# seven_seg_thermistor_one.net
KiCad netlist of a schematic drawn in EAGLE
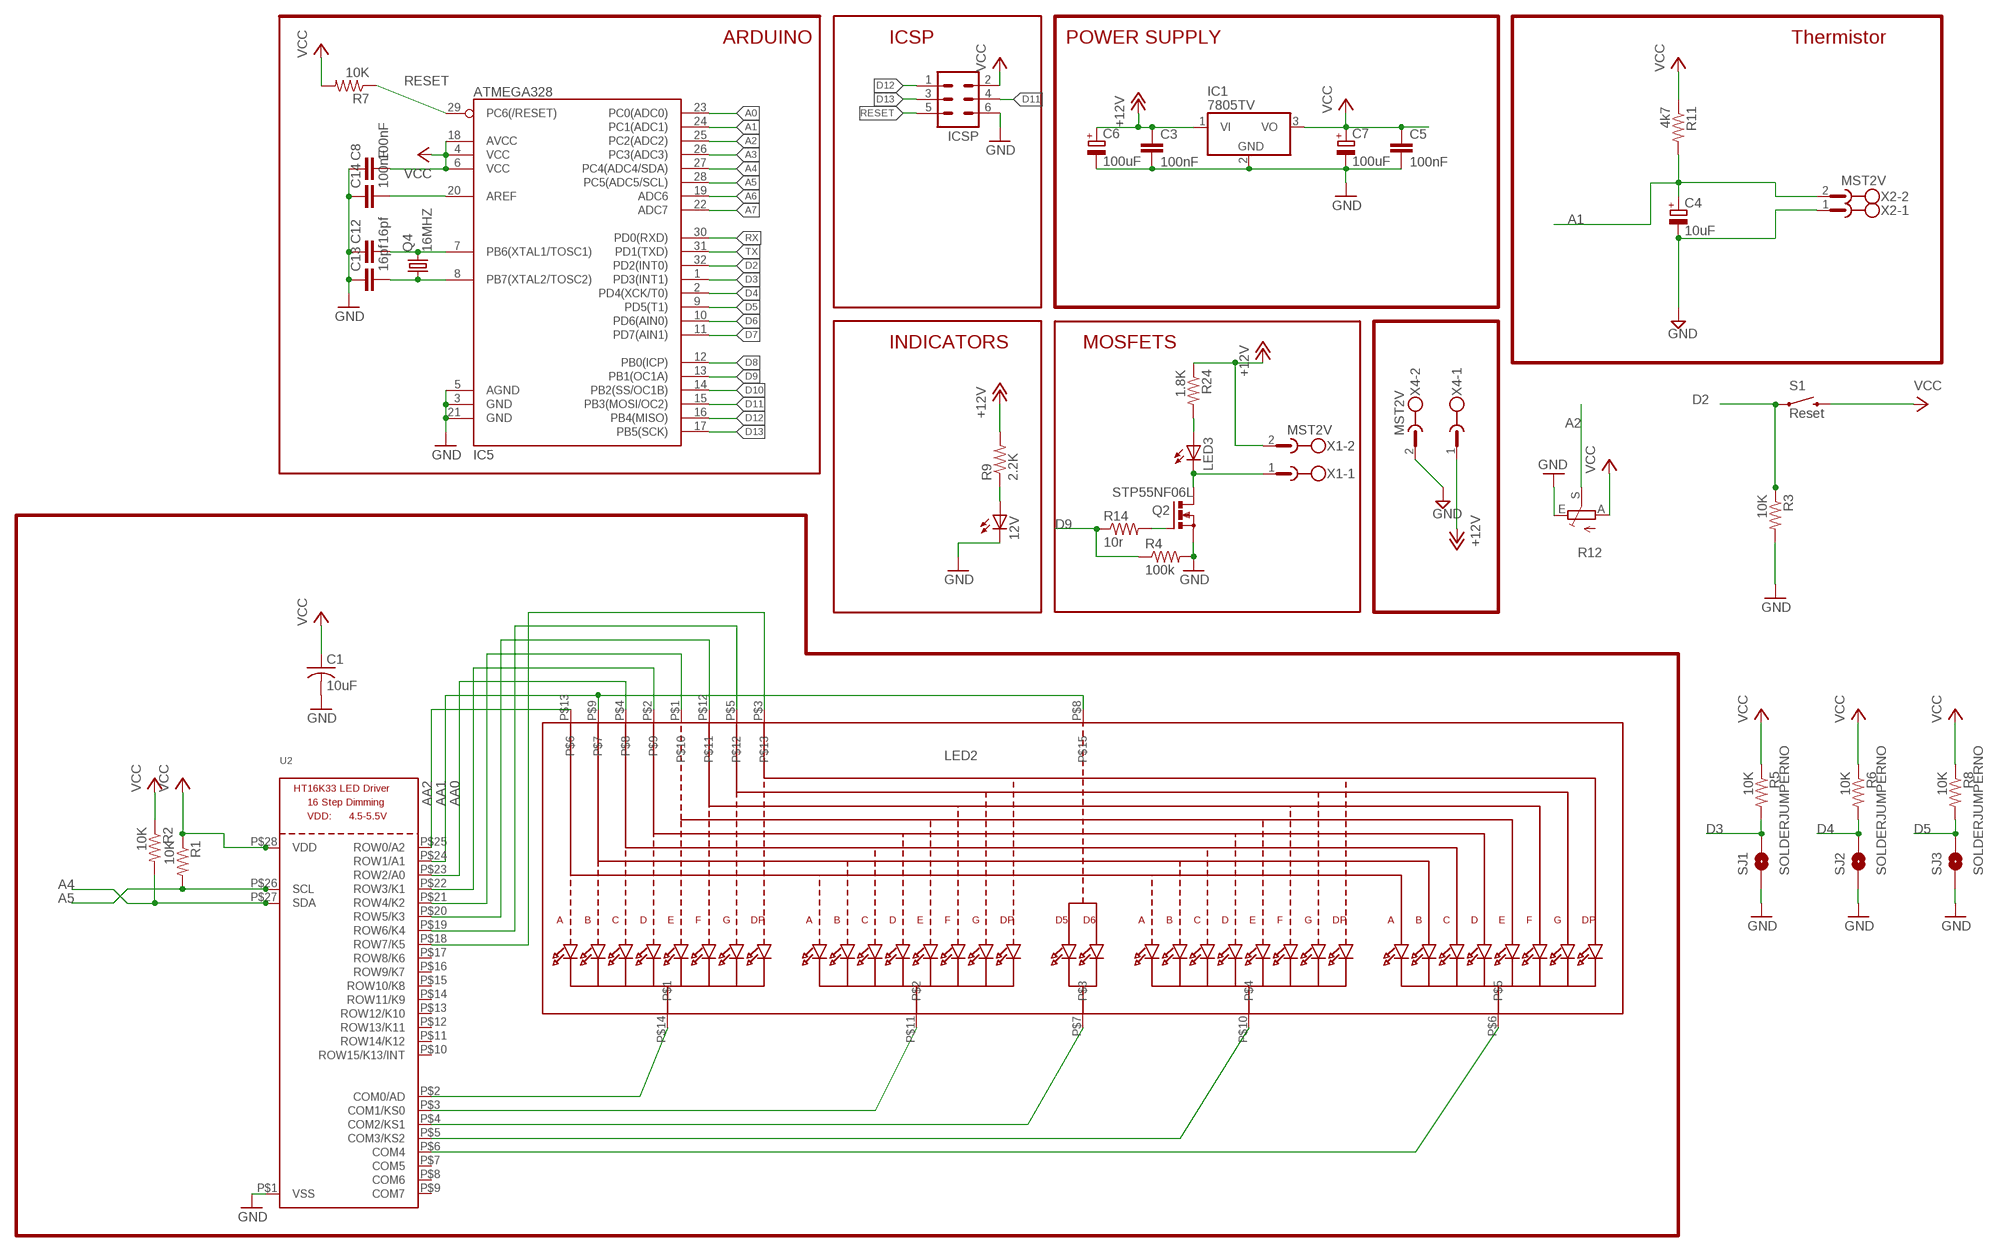
[diagram p0: schematic, sheet 1]

(export (version "E")
  (design (tool "Eeschema 10.0.6"))
  (components
    (comp (ref "12V")
      (value "LED0805")
      (footprint "eagle-import:LED-0805")
      (libsource (lib "eagle-import") (part "LED0805"))
    )
    (comp (ref "C1")
      (value "10uF")
      (footprint "eagle-import:C0805K")
      (libsource (lib "eagle-import") (part "C-USC0805K"))
    )
    (comp (ref "C3")
      (value "100nF")
      (footprint "eagle-import:0805")
      (libsource (lib "eagle-import") (part "CAP0805"))
    )
    (comp (ref "C4")
      (value "10uF")
      (footprint "eagle-import:E5-6")
      (libsource (lib "eagle-import") (part "CPOL-EUE5-6"))
    )
    (comp (ref "C5")
      (value "100nF")
      (footprint "eagle-import:0805")
      (libsource (lib "eagle-import") (part "CAP0805"))
    )
    (comp (ref "C6")
      (value "100uF")
      (footprint "eagle-import:E3,5-8")
      (libsource (lib "eagle-import") (part "CPOL-EUE3.5-8"))
    )
    (comp (ref "C7")
      (value "100uF")
      (footprint "eagle-import:E3,5-8")
      (libsource (lib "eagle-import") (part "CPOL-EUE3.5-8"))
    )
    (comp (ref "C8")
      (value "100nF")
      (footprint "eagle-import:0805")
      (libsource (lib "eagle-import") (part "CAP0805"))
    )
    (comp (ref "C12")
      (value "16pf")
      (footprint "eagle-import:0805")
      (libsource (lib "eagle-import") (part "CAP0805"))
    )
    (comp (ref "C13")
      (value "16pf")
      (footprint "eagle-import:0805")
      (libsource (lib "eagle-import") (part "CAP0805"))
    )
    (comp (ref "C14")
      (value "100nF")
      (footprint "eagle-import:0805")
      (libsource (lib "eagle-import") (part "CAP0805"))
    )
    (comp (ref "IC1")
      (value "7805TV")
      (footprint "eagle-import:TO220V")
      (libsource (lib "eagle-import") (part "78TV05"))
    )
    (comp (ref "IC5")
      (value "ATMEGA328")
      (footprint "eagle-import:TQFP32-08")
      (libsource (lib "eagle-import") (part "ATMEGA168"))
    )
    (comp (ref "ICSP")
      (value "ML6")
      (footprint "eagle-import:ML6")
      (libsource (lib "eagle-import") (part "ML6"))
    )
    (comp (ref "LED2")
      (value "DISP_SEGMENT_4DIGIT_BL-Q56C43")
      (footprint "eagle-import:SEGMENT-BL-Q56C43")
      (libsource (lib "eagle-import") (part "DISP_SEGMENT_4DIGIT_BL-Q56C43"))
    )
    (comp (ref "LED3")
      (value "LEDCHIP-LED0805")
      (footprint "eagle-import:CHIP-LED0805")
      (libsource (lib "eagle-import") (part "LEDCHIP-LED0805"))
    )
    (comp (ref "Q2")
      (value "STP55NF06L")
      (footprint "eagle-import:TO220BV")
      (libsource (lib "eagle-import") (part "IRF512"))
    )
    (comp (ref "Q4")
      (value "16MHZ")
      (footprint "eagle-import:HC49_S")
      (libsource (lib "eagle-import") (part "CRYSTALHC49S"))
    )
    (comp (ref "R1")
      (value "10K")
      (footprint "eagle-import:R0805")
      (libsource (lib "eagle-import") (part "R-US_R0805"))
    )
    (comp (ref "R2")
      (value "10K")
      (footprint "eagle-import:R0805")
      (libsource (lib "eagle-import") (part "R-US_R0805"))
    )
    (comp (ref "R3")
      (value "10K")
      (footprint "eagle-import:0805")
      (libsource (lib "eagle-import") (part "RESISTOR"))
    )
    (comp (ref "R4")
      (value "100k")
      (footprint "eagle-import:R0805")
      (libsource (lib "eagle-import") (part "R-US_R0805"))
    )
    (comp (ref "R5")
      (value "10K")
      (footprint "eagle-import:0805")
      (libsource (lib "eagle-import") (part "RESISTOR"))
    )
    (comp (ref "R6")
      (value "10K")
      (footprint "eagle-import:0805")
      (libsource (lib "eagle-import") (part "RESISTOR"))
    )
    (comp (ref "R7")
      (value "10K")
      (footprint "eagle-import:0805")
      (libsource (lib "eagle-import") (part "RESISTOR"))
    )
    (comp (ref "R8")
      (value "10K")
      (footprint "eagle-import:0805")
      (libsource (lib "eagle-import") (part "RESISTOR"))
    )
    (comp (ref "R9")
      (value "2.2K")
      (footprint "eagle-import:0805")
      (libsource (lib "eagle-import") (part "RESISTOR"))
    )
    (comp (ref "R11")
      (value "4k7")
      (footprint "eagle-import:0805")
      (libsource (lib "eagle-import") (part "RESISTOR"))
    )
    (comp (ref "R12")
      (value "TRIM_EU-B25U")
      (footprint "eagle-import:B25U")
      (libsource (lib "eagle-import") (part "TRIM_EU-B25U"))
    )
    (comp (ref "R14")
      (value "10r")
      (footprint "eagle-import:M0805")
      (libsource (lib "eagle-import") (part "resistor_R-US_M0805"))
    )
    (comp (ref "R24")
      (value "1.8K")
      (footprint "eagle-import:R0805")
      (libsource (lib "eagle-import") (part "R-US_R0805"))
    )
    (comp (ref "S1")
      (value "Reset")
      (footprint "eagle-import:TACTILE-SWITCH-SMD-ALT01")
      (libsource (lib "eagle-import") (part "SWITCH-MOMENTARY-2SMD-ALT01"))
    )
    (comp (ref "SJ1")
      (value "SOLDERJUMPERNO")
      (footprint "eagle-import:SJ_2S-NO")
      (libsource (lib "eagle-import") (part "SOLDERJUMPERNO"))
    )
    (comp (ref "SJ2")
      (value "SOLDERJUMPERNO")
      (footprint "eagle-import:SJ_2S-NO")
      (libsource (lib "eagle-import") (part "SOLDERJUMPERNO"))
    )
    (comp (ref "SJ3")
      (value "SOLDERJUMPERNO")
      (footprint "eagle-import:SJ_2S-NO")
      (libsource (lib "eagle-import") (part "SOLDERJUMPERNO"))
    )
    (comp (ref "U2")
      (value "HT16K33_SOP28")
      (footprint "eagle-import:SOP28_300MIL")
      (libsource (lib "eagle-import") (part "HT16K33_SOP28"))
    )
    (comp (ref "X1")
      (value "MST2V")
      (footprint "eagle-import:MSTBV2")
      (libsource (lib "eagle-import") (part "MST2V"))
    )
    (comp (ref "X2")
      (value "MST2V")
      (footprint "eagle-import:MSTBV2")
      (libsource (lib "eagle-import") (part "MST2V"))
    )
    (comp (ref "X4")
      (value "MST2V")
      (footprint "eagle-import:MSTBV2")
      (libsource (lib "eagle-import") (part "MST2V"))
    )
  )
  (nets
    (net (code "1") (name "+12V") (class "Default")
      (node (ref "C3") (pin "1") (pinfunction "1_1") (pintype "passive"))
      (node (ref "C6") (pin "+") (pinfunction "+_+") (pintype "passive"))
      (node (ref "IC1") (pin "1") (pinfunction "VI_1") (pintype "input"))
      (node (ref "R24") (pin "1") (pinfunction "1_1") (pintype "passive"))
      (node (ref "R9") (pin "2") (pinfunction "2_2") (pintype "passive"))
      (node (ref "X1") (pin "2") (pinfunction "1_2") (pintype "passive"))
      (node (ref "X4") (pin "1") (pinfunction "1_1") (pintype "passive"))
    )
    (net (code "2") (name "/AA0") (class "Default")
      (node (ref "LED2") (pin "P$4") (pinfunction "P$8_P$4") (pintype "bidirectional"))
      (node (ref "U2") (pin "P$23") (pinfunction "ROW2/A0_P$23") (pintype "bidirectional"))
    )
    (net (code "3") (name "/AA1") (class "Default")
      (node (ref "LED2") (pin "P$8") (pinfunction "P$15_P$8") (pintype "bidirectional"))
      (node (ref "LED2") (pin "P$9") (pinfunction "P$7_P$9") (pintype "bidirectional"))
      (node (ref "U2") (pin "P$24") (pinfunction "ROW1/A1_P$24") (pintype "bidirectional"))
    )
    (net (code "4") (name "/AA2") (class "Default")
      (node (ref "LED2") (pin "P$13") (pinfunction "P$6_P$13") (pintype "bidirectional"))
      (node (ref "U2") (pin "P$25") (pinfunction "ROW0/A2_P$25") (pintype "bidirectional"))
    )
    (net (code "5") (name "A0") (class "Default")
      (node (ref "IC5") (pin "23") (pinfunction "PC0(ADC0)_23") (pintype "bidirectional"))
    )
    (net (code "6") (name "A1") (class "Default")
      (node (ref "C4") (pin "+") (pinfunction "+_+") (pintype "passive"))
      (node (ref "IC5") (pin "24") (pinfunction "PC1(ADC1)_24") (pintype "bidirectional"))
      (node (ref "R11") (pin "2") (pinfunction "2_2") (pintype "passive"))
      (node (ref "X2") (pin "2") (pinfunction "1_2") (pintype "passive"))
    )
    (net (code "7") (name "A2") (class "Default")
      (node (ref "IC5") (pin "25") (pinfunction "PC2(ADC2)_25") (pintype "bidirectional"))
      (node (ref "R12") (pin "S") (pinfunction "S_S") (pintype "passive"))
    )
    (net (code "8") (name "A3") (class "Default")
      (node (ref "IC5") (pin "26") (pinfunction "PC3(ADC3)_26") (pintype "bidirectional"))
    )
    (net (code "9") (name "A4") (class "Default")
      (node (ref "IC5") (pin "27") (pinfunction "PC4(ADC4/SDA)_27") (pintype "bidirectional"))
      (node (ref "R2") (pin "2") (pinfunction "2_2") (pintype "passive"))
      (node (ref "U2") (pin "P$27") (pinfunction "SDA_P$27") (pintype "bidirectional"))
    )
    (net (code "10") (name "A5") (class "Default")
      (node (ref "IC5") (pin "28") (pinfunction "PC5(ADC5/SCL)_28") (pintype "bidirectional"))
      (node (ref "R1") (pin "2") (pinfunction "2_2") (pintype "passive"))
      (node (ref "U2") (pin "P$26") (pinfunction "SCL_P$26") (pintype "bidirectional"))
    )
    (net (code "11") (name "A6") (class "Default")
      (node (ref "IC5") (pin "19") (pinfunction "ADC6_19") (pintype "bidirectional"))
    )
    (net (code "12") (name "A7") (class "Default")
      (node (ref "IC5") (pin "22") (pinfunction "ADC7_22") (pintype "bidirectional"))
    )
    (net (code "13") (name "D2") (class "Default")
      (node (ref "IC5") (pin "32") (pinfunction "PD2(INT0)_32") (pintype "bidirectional"))
      (node (ref "R3") (pin "1") (pinfunction "1_1") (pintype "passive"))
      (node (ref "S1") (pin "1") (pinfunction "1_1") (pintype "passive"))
      (node (ref "S1") (pin "2") (pinfunction "1_2") (pintype "passive"))
    )
    (net (code "14") (name "D3") (class "Default")
      (node (ref "IC5") (pin "1") (pinfunction "PD3(INT1)_1") (pintype "bidirectional"))
      (node (ref "R5") (pin "2") (pinfunction "2_2") (pintype "passive"))
      (node (ref "SJ1") (pin "2") (pinfunction "2_2") (pintype "passive"))
    )
    (net (code "15") (name "D4") (class "Default")
      (node (ref "IC5") (pin "2") (pinfunction "PD4(XCK/T0)_2") (pintype "bidirectional"))
      (node (ref "R6") (pin "2") (pinfunction "2_2") (pintype "passive"))
      (node (ref "SJ2") (pin "2") (pinfunction "2_2") (pintype "passive"))
    )
    (net (code "16") (name "D5") (class "Default")
      (node (ref "IC5") (pin "9") (pinfunction "PD5(T1)_9") (pintype "bidirectional"))
      (node (ref "R8") (pin "2") (pinfunction "2_2") (pintype "passive"))
      (node (ref "SJ3") (pin "2") (pinfunction "2_2") (pintype "passive"))
    )
    (net (code "17") (name "D6") (class "Default")
      (node (ref "IC5") (pin "10") (pinfunction "PD6(AIN0)_10") (pintype "bidirectional"))
    )
    (net (code "18") (name "D7") (class "Default")
      (node (ref "IC5") (pin "11") (pinfunction "PD7(AIN1)_11") (pintype "bidirectional"))
    )
    (net (code "19") (name "D8") (class "Default")
      (node (ref "IC5") (pin "12") (pinfunction "PB0(ICP)_12") (pintype "bidirectional"))
    )
    (net (code "20") (name "D9") (class "Default")
      (node (ref "IC5") (pin "13") (pinfunction "PB1(OC1A)_13") (pintype "bidirectional"))
      (node (ref "R14") (pin "1") (pinfunction "1_1") (pintype "passive"))
      (node (ref "R4") (pin "1") (pinfunction "1_1") (pintype "passive"))
    )
    (net (code "21") (name "D10") (class "Default")
      (node (ref "IC5") (pin "14") (pinfunction "PB2(SS/OC1B)_14") (pintype "bidirectional"))
    )
    (net (code "22") (name "D11") (class "Default")
      (node (ref "IC5") (pin "15") (pinfunction "PB3(MOSI/OC2)_15") (pintype "bidirectional"))
      (node (ref "ICSP") (pin "4") (pinfunction "4_4") (pintype "passive"))
    )
    (net (code "23") (name "D12") (class "Default")
      (node (ref "IC5") (pin "16") (pinfunction "PB4(MISO)_16") (pintype "bidirectional"))
      (node (ref "ICSP") (pin "1") (pinfunction "1_1") (pintype "passive"))
    )
    (net (code "24") (name "D13") (class "Default")
      (node (ref "IC5") (pin "17") (pinfunction "PB5(SCK)_17") (pintype "bidirectional"))
      (node (ref "ICSP") (pin "3") (pinfunction "3_3") (pintype "passive"))
    )
    (net (code "25") (name "GND") (class "Default")
      (node (ref "12V") (pin "C") (pinfunction "C_C") (pintype "passive"))
      (node (ref "C1") (pin "2") (pinfunction "2_2") (pintype "passive"))
      (node (ref "C12") (pin "1") (pinfunction "1_1") (pintype "passive"))
      (node (ref "C13") (pin "1") (pinfunction "1_1") (pintype "passive"))
      (node (ref "C14") (pin "1") (pinfunction "1_1") (pintype "passive"))
      (node (ref "C3") (pin "2") (pinfunction "2_2") (pintype "passive"))
      (node (ref "C4") (pin "-") (pinfunction "-_-") (pintype "passive"))
      (node (ref "C5") (pin "2") (pinfunction "2_2") (pintype "passive"))
      (node (ref "C6") (pin "-") (pinfunction "-_-") (pintype "passive"))
      (node (ref "C7") (pin "-") (pinfunction "-_-") (pintype "passive"))
      (node (ref "C8") (pin "1") (pinfunction "1_1") (pintype "passive"))
      (node (ref "IC1") (pin "2") (pinfunction "GND_2") (pintype "passive"))
      (node (ref "IC5") (pin "21") (pinfunction "GND_21") (pintype "bidirectional"))
      (node (ref "IC5") (pin "3") (pinfunction "GND_3") (pintype "bidirectional"))
      (node (ref "IC5") (pin "5") (pinfunction "AGND_5") (pintype "bidirectional"))
      (node (ref "ICSP") (pin "6") (pinfunction "6_6") (pintype "passive"))
      (node (ref "Q2") (pin "S") (pinfunction "S_S") (pintype "passive"))
      (node (ref "R12") (pin "E") (pinfunction "E_E") (pintype "passive"))
      (node (ref "R3") (pin "2") (pinfunction "2_2") (pintype "passive"))
      (node (ref "R4") (pin "2") (pinfunction "2_2") (pintype "passive"))
      (node (ref "SJ1") (pin "1") (pinfunction "1_1") (pintype "passive"))
      (node (ref "SJ2") (pin "1") (pinfunction "1_1") (pintype "passive"))
      (node (ref "SJ3") (pin "1") (pinfunction "1_1") (pintype "passive"))
      (node (ref "U2") (pin "P$1") (pinfunction "VSS_P$1") (pintype "bidirectional"))
      (node (ref "X2") (pin "1") (pinfunction "1_1") (pintype "passive"))
      (node (ref "X4") (pin "2") (pinfunction "1_2") (pintype "passive"))
    )
    (net (code "26") (name "Net-(12V-PadA)") (class "Default")
      (node (ref "12V") (pin "A") (pinfunction "A_A") (pintype "passive"))
      (node (ref "R9") (pin "1") (pinfunction "1_1") (pintype "passive"))
    )
    (net (code "27") (name "Net-(IC5-AREF)") (class "Default")
      (node (ref "C14") (pin "2") (pinfunction "2_2") (pintype "passive"))
      (node (ref "IC5") (pin "20") (pinfunction "AREF_20") (pintype "bidirectional"))
    )
    (net (code "28") (name "Net-(IC5-PB6(XTAL1{slash}TOSC1))") (class "Default")
      (node (ref "C12") (pin "2") (pinfunction "2_2") (pintype "passive"))
      (node (ref "IC5") (pin "7") (pinfunction "PB6(XTAL1/TOSC1)_7") (pintype "bidirectional"))
      (node (ref "Q4") (pin "2") (pinfunction "2_2") (pintype "passive"))
    )
    (net (code "29") (name "Net-(IC5-PB7(XTAL2{slash}TOSC2))") (class "Default")
      (node (ref "C13") (pin "2") (pinfunction "2_2") (pintype "passive"))
      (node (ref "IC5") (pin "8") (pinfunction "PB7(XTAL2/TOSC2)_8") (pintype "bidirectional"))
      (node (ref "Q4") (pin "1") (pinfunction "1_1") (pintype "passive"))
    )
    (net (code "30") (name "Net-(LED2-P$1)") (class "Default")
      (node (ref "LED2") (pin "P$14") (pinfunction "P$1_P$14") (pintype "bidirectional"))
      (node (ref "U2") (pin "P$2") (pinfunction "COM0/AD_P$2") (pintype "bidirectional"))
    )
    (net (code "31") (name "Net-(LED2-P$2)") (class "Default")
      (node (ref "LED2") (pin "P$11") (pinfunction "P$2_P$11") (pintype "bidirectional"))
      (node (ref "U2") (pin "P$3") (pinfunction "COM1/KS0_P$3") (pintype "bidirectional"))
    )
    (net (code "32") (name "Net-(LED2-P$3)") (class "Default")
      (node (ref "LED2") (pin "P$7") (pinfunction "P$3_P$7") (pintype "bidirectional"))
      (node (ref "U2") (pin "P$4") (pinfunction "COM2/KS1_P$4") (pintype "bidirectional"))
    )
    (net (code "33") (name "Net-(LED2-P$4)") (class "Default")
      (node (ref "LED2") (pin "P$10") (pinfunction "P$4_P$10") (pintype "bidirectional"))
      (node (ref "U2") (pin "P$5") (pinfunction "COM3/KS2_P$5") (pintype "bidirectional"))
    )
    (net (code "34") (name "Net-(LED2-P$5)") (class "Default")
      (node (ref "LED2") (pin "P$6") (pinfunction "P$5_P$6") (pintype "bidirectional"))
      (node (ref "U2") (pin "P$6") (pinfunction "COM4_P$6") (pintype "bidirectional"))
    )
    (net (code "35") (name "Net-(LED2-P$9)") (class "Default")
      (node (ref "LED2") (pin "P$2") (pinfunction "P$9_P$2") (pintype "bidirectional"))
      (node (ref "U2") (pin "P$22") (pinfunction "ROW3/K1_P$22") (pintype "bidirectional"))
    )
    (net (code "36") (name "Net-(LED2-P$10)") (class "Default")
      (node (ref "LED2") (pin "P$1") (pinfunction "P$10_P$1") (pintype "bidirectional"))
      (node (ref "U2") (pin "P$21") (pinfunction "ROW4/K2_P$21") (pintype "bidirectional"))
    )
    (net (code "37") (name "Net-(LED2-P$11)") (class "Default")
      (node (ref "LED2") (pin "P$12") (pinfunction "P$11_P$12") (pintype "bidirectional"))
      (node (ref "U2") (pin "P$20") (pinfunction "ROW5/K3_P$20") (pintype "bidirectional"))
    )
    (net (code "38") (name "Net-(LED2-P$12)") (class "Default")
      (node (ref "LED2") (pin "P$5") (pinfunction "P$12_P$5") (pintype "bidirectional"))
      (node (ref "U2") (pin "P$19") (pinfunction "ROW6/K4_P$19") (pintype "bidirectional"))
    )
    (net (code "39") (name "Net-(LED2-P$13)") (class "Default")
      (node (ref "LED2") (pin "P$3") (pinfunction "P$13_P$3") (pintype "bidirectional"))
      (node (ref "U2") (pin "P$18") (pinfunction "ROW7/K5_P$18") (pintype "bidirectional"))
    )
    (net (code "40") (name "Net-(LED3-PadA)") (class "Default")
      (node (ref "LED3") (pin "A") (pinfunction "A_A") (pintype "passive"))
      (node (ref "R24") (pin "2") (pinfunction "2_2") (pintype "passive"))
    )
    (net (code "41") (name "Net-(LED3-PadC)") (class "Default")
      (node (ref "LED3") (pin "C") (pinfunction "C_C") (pintype "passive"))
      (node (ref "Q2") (pin "D") (pinfunction "D_D") (pintype "passive"))
      (node (ref "X1") (pin "1") (pinfunction "1_1") (pintype "passive"))
    )
    (net (code "42") (name "Net-(Q2-PadG)") (class "Default")
      (node (ref "Q2") (pin "G") (pinfunction "G_G") (pintype "passive"))
      (node (ref "R14") (pin "2") (pinfunction "2_2") (pintype "passive"))
    )
    (net (code "43") (name "RESET") (class "Default")
      (node (ref "IC5") (pin "29") (pinfunction "PC6(/RESET)_29") (pintype "bidirectional"))
      (node (ref "ICSP") (pin "5") (pinfunction "5_5") (pintype "passive"))
      (node (ref "R7") (pin "1") (pinfunction "1_1") (pintype "passive"))
    )
    (net (code "44") (name "RX") (class "Default")
      (node (ref "IC5") (pin "30") (pinfunction "PD0(RXD)_30") (pintype "bidirectional"))
    )
    (net (code "45") (name "TX") (class "Default")
      (node (ref "IC5") (pin "31") (pinfunction "PD1(TXD)_31") (pintype "bidirectional"))
    )
    (net (code "46") (name "VCC") (class "Default")
      (node (ref "C1") (pin "1") (pinfunction "1_1") (pintype "passive"))
      (node (ref "C5") (pin "1") (pinfunction "1_1") (pintype "passive"))
      (node (ref "C7") (pin "+") (pinfunction "+_+") (pintype "passive"))
      (node (ref "C8") (pin "2") (pinfunction "2_2") (pintype "passive"))
      (node (ref "IC1") (pin "3") (pinfunction "VO_3") (pintype "passive"))
      (node (ref "IC5") (pin "18") (pinfunction "AVCC_18") (pintype "bidirectional"))
      (node (ref "IC5") (pin "4") (pinfunction "VCC_4") (pintype "bidirectional"))
      (node (ref "IC5") (pin "6") (pinfunction "VCC_6") (pintype "bidirectional"))
      (node (ref "ICSP") (pin "2") (pinfunction "2_2") (pintype "passive"))
      (node (ref "R1") (pin "1") (pinfunction "1_1") (pintype "passive"))
      (node (ref "R11") (pin "1") (pinfunction "1_1") (pintype "passive"))
      (node (ref "R12") (pin "A") (pinfunction "A_A") (pintype "passive"))
      (node (ref "R2") (pin "1") (pinfunction "1_1") (pintype "passive"))
      (node (ref "R5") (pin "1") (pinfunction "1_1") (pintype "passive"))
      (node (ref "R6") (pin "1") (pinfunction "1_1") (pintype "passive"))
      (node (ref "R7") (pin "2") (pinfunction "2_2") (pintype "passive"))
      (node (ref "R8") (pin "1") (pinfunction "1_1") (pintype "passive"))
      (node (ref "S1") (pin "3") (pinfunction "2_3") (pintype "passive"))
      (node (ref "S1") (pin "4") (pinfunction "2_4") (pintype "passive"))
      (node (ref "U2") (pin "P$28") (pinfunction "VDD_P$28") (pintype "bidirectional"))
    )
    (net (code "47") (name "unconnected-(U2-COM5-PadP$7)") (class "Default")
      (node (ref "U2") (pin "P$7") (pinfunction "COM5_P$7") (pintype "bidirectional"))
    )
    (net (code "48") (name "unconnected-(U2-COM6-PadP$8)") (class "Default")
      (node (ref "U2") (pin "P$8") (pinfunction "COM6_P$8") (pintype "bidirectional"))
    )
    (net (code "49") (name "unconnected-(U2-COM7-PadP$9)") (class "Default")
      (node (ref "U2") (pin "P$9") (pinfunction "COM7_P$9") (pintype "bidirectional"))
    )
    (net (code "50") (name "unconnected-(U2-ROW8{slash}K6-PadP$17)") (class "Default")
      (node (ref "U2") (pin "P$17") (pinfunction "ROW8/K6_P$17") (pintype "bidirectional"))
    )
    (net (code "51") (name "unconnected-(U2-ROW9{slash}K7-PadP$16)") (class "Default")
      (node (ref "U2") (pin "P$16") (pinfunction "ROW9/K7_P$16") (pintype "bidirectional"))
    )
    (net (code "52") (name "unconnected-(U2-ROW10{slash}K8-PadP$15)") (class "Default")
      (node (ref "U2") (pin "P$15") (pinfunction "ROW10/K8_P$15") (pintype "bidirectional"))
    )
    (net (code "53") (name "unconnected-(U2-ROW11{slash}K9-PadP$14)") (class "Default")
      (node (ref "U2") (pin "P$14") (pinfunction "ROW11/K9_P$14") (pintype "bidirectional"))
    )
    (net (code "54") (name "unconnected-(U2-ROW12{slash}K10-PadP$13)") (class "Default")
      (node (ref "U2") (pin "P$13") (pinfunction "ROW12/K10_P$13") (pintype "bidirectional"))
    )
    (net (code "55") (name "unconnected-(U2-ROW13{slash}K11-PadP$12)") (class "Default")
      (node (ref "U2") (pin "P$12") (pinfunction "ROW13/K11_P$12") (pintype "bidirectional"))
    )
    (net (code "56") (name "unconnected-(U2-ROW14{slash}K12-PadP$11)") (class "Default")
      (node (ref "U2") (pin "P$11") (pinfunction "ROW14/K12_P$11") (pintype "bidirectional"))
    )
    (net (code "57") (name "unconnected-(U2-ROW15{slash}K13{slash}INT-PadP$10)") (class "Default")
      (node (ref "U2") (pin "P$10") (pinfunction "ROW15/K13/INT_P$10") (pintype "bidirectional"))
    )
  )
)
